# LEDMulti.net
KiCad netlist of a schematic drawn in Altium Designer
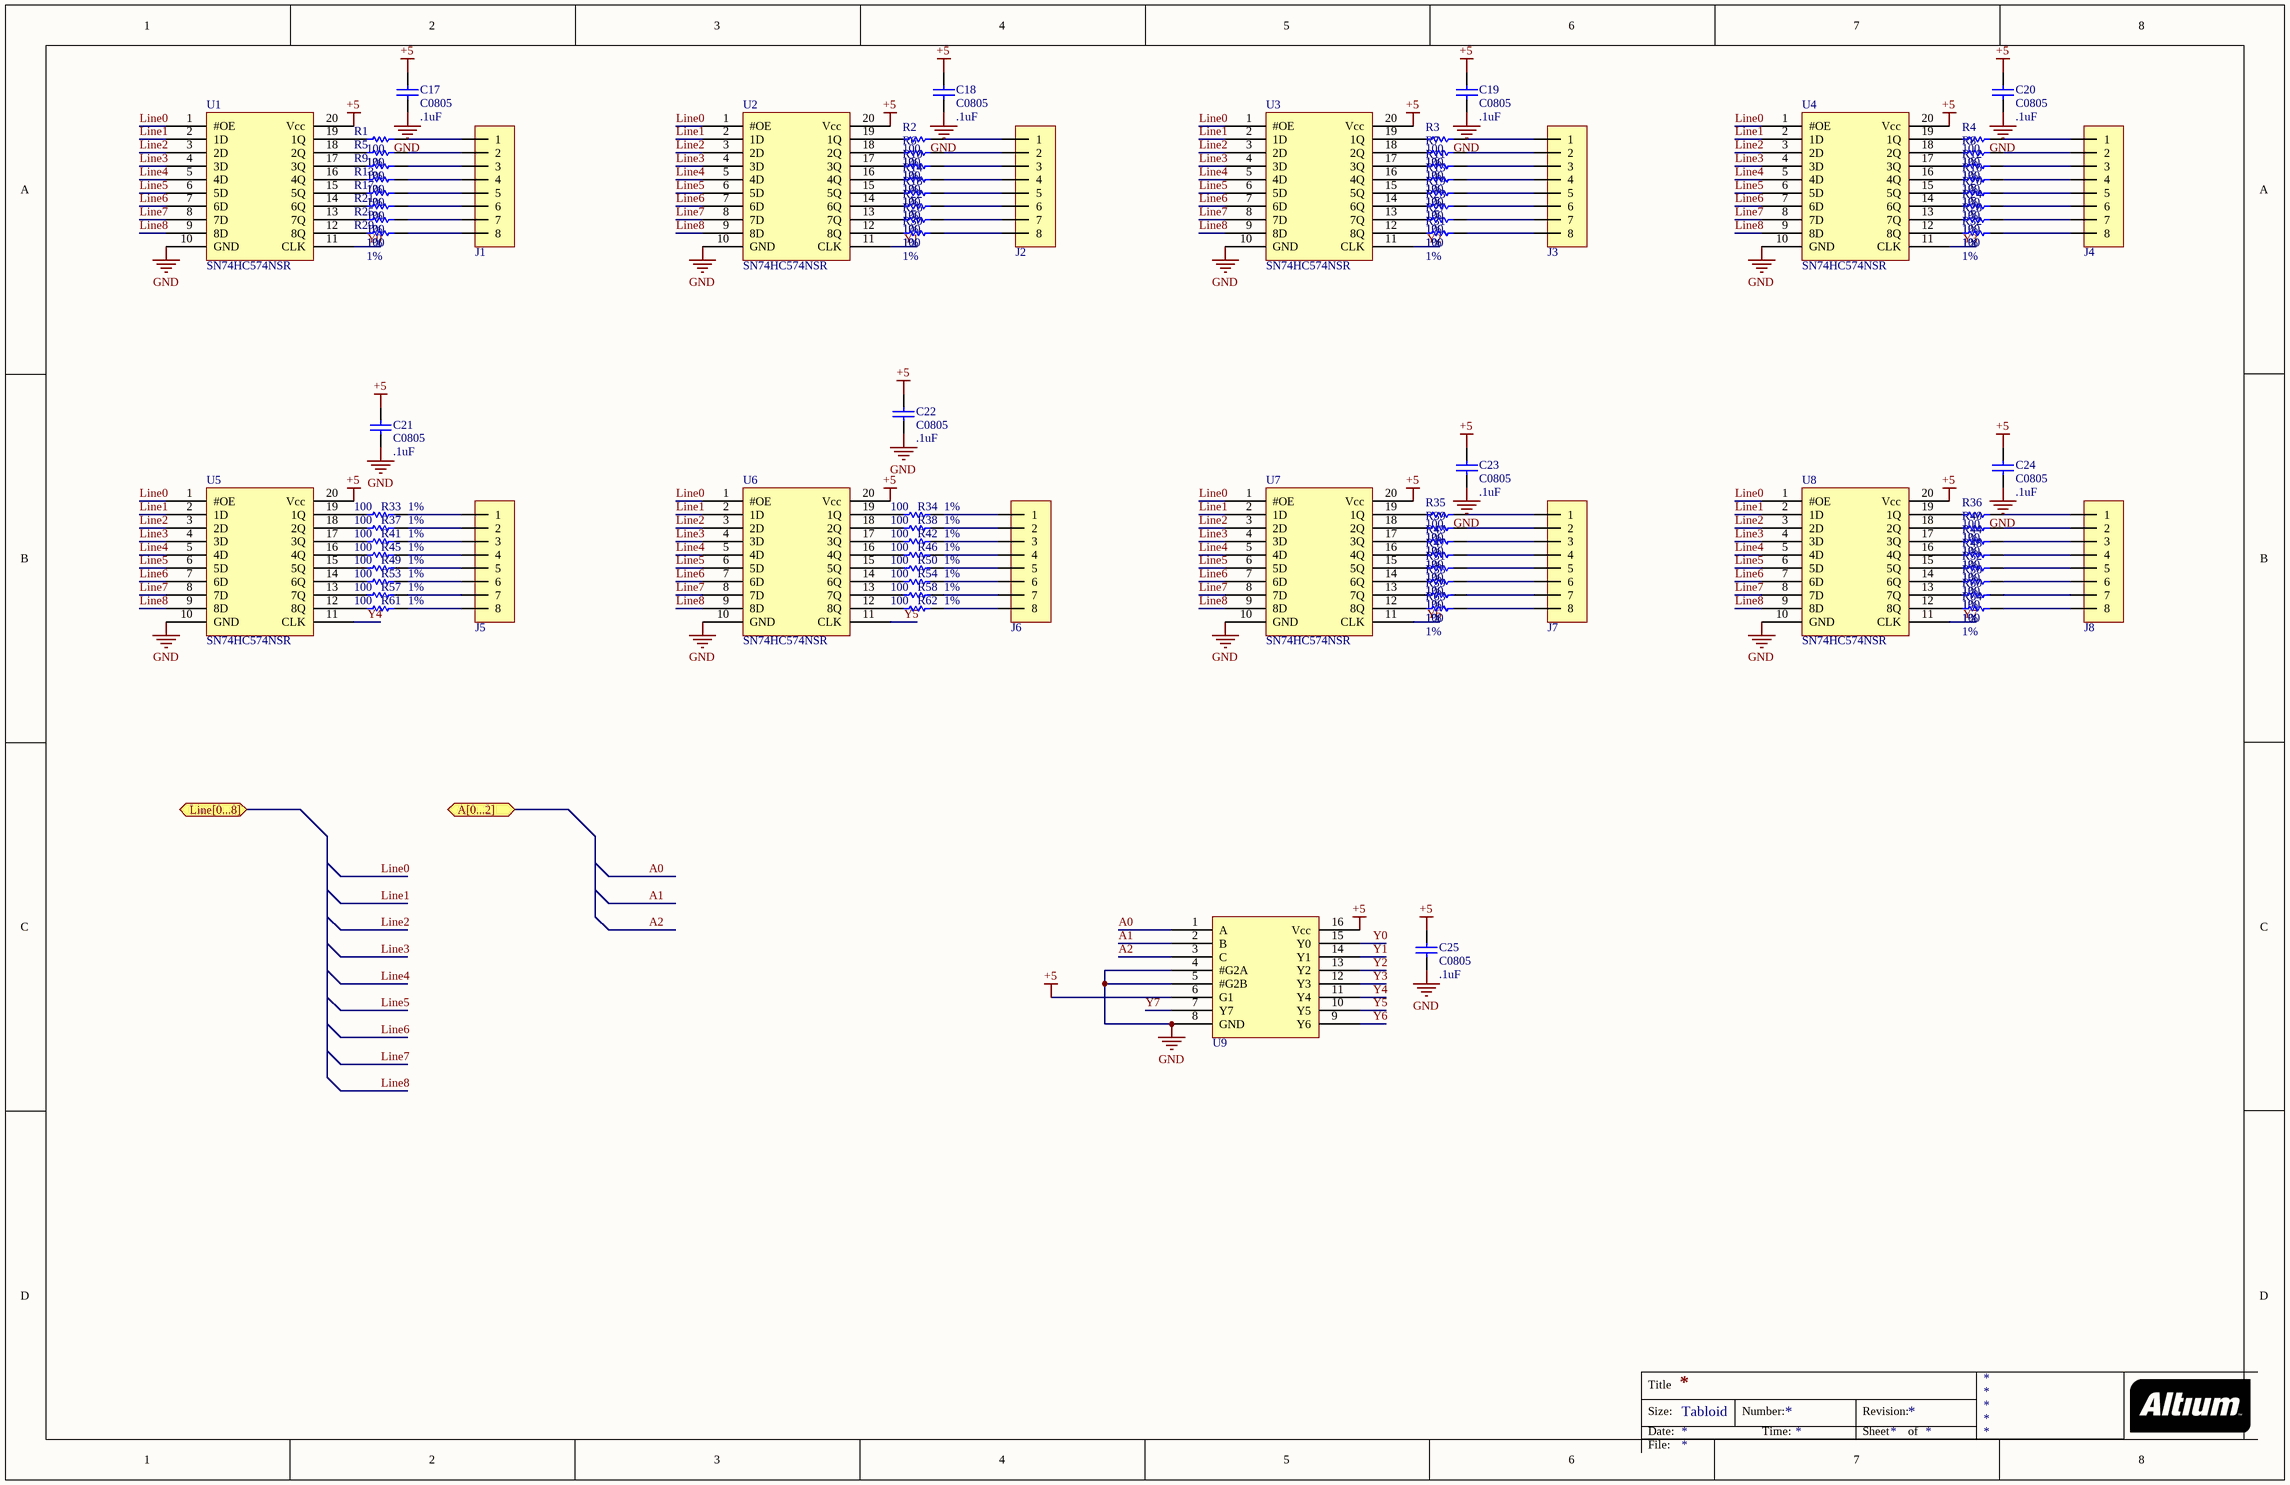
[diagram p0: LEDMulti.SchDoc]

(export (version "E")
  (design (tool "Eeschema 10.0.6"))
  (components
    (comp (ref "C17")
      (value "C0805")
      (footprint "0805")
      (description "Ceramic Chip Capacitor - Standard")
      (fields (field (name "ALTIUM_VALUE") ".1uF") (field (name "PUBLISHER") "Altium Limited"))
      (libsource (lib "KEMET Chip Capacitor") (part "C0805"))
    )
    (comp (ref "C18")
      (value "C0805")
      (footprint "0805")
      (description "Ceramic Chip Capacitor - Standard")
      (fields (field (name "ALTIUM_VALUE") ".1uF") (field (name "PUBLISHER") "Altium Limited"))
      (libsource (lib "KEMET Chip Capacitor") (part "C0805"))
    )
    (comp (ref "C19")
      (value "C0805")
      (footprint "0805")
      (description "Ceramic Chip Capacitor - Standard")
      (fields (field (name "ALTIUM_VALUE") ".1uF") (field (name "PUBLISHER") "Altium Limited"))
      (libsource (lib "KEMET Chip Capacitor") (part "C0805"))
    )
    (comp (ref "C20")
      (value "C0805")
      (footprint "0805")
      (description "Ceramic Chip Capacitor - Standard")
      (fields (field (name "ALTIUM_VALUE") ".1uF") (field (name "PUBLISHER") "Altium Limited"))
      (libsource (lib "KEMET Chip Capacitor") (part "C0805"))
    )
    (comp (ref "C21")
      (value "C0805")
      (footprint "0805")
      (description "Ceramic Chip Capacitor - Standard")
      (fields (field (name "ALTIUM_VALUE") ".1uF") (field (name "PUBLISHER") "Altium Limited"))
      (libsource (lib "KEMET Chip Capacitor") (part "C0805"))
    )
    (comp (ref "C22")
      (value "C0805")
      (footprint "0805")
      (description "Ceramic Chip Capacitor - Standard")
      (fields (field (name "ALTIUM_VALUE") ".1uF") (field (name "PUBLISHER") "Altium Limited"))
      (libsource (lib "KEMET Chip Capacitor") (part "C0805"))
    )
    (comp (ref "C23")
      (value "C0805")
      (footprint "0805")
      (description "Ceramic Chip Capacitor - Standard")
      (fields (field (name "ALTIUM_VALUE") ".1uF") (field (name "PUBLISHER") "Altium Limited"))
      (libsource (lib "KEMET Chip Capacitor") (part "C0805"))
    )
    (comp (ref "C24")
      (value "C0805")
      (footprint "0805")
      (description "Ceramic Chip Capacitor - Standard")
      (fields (field (name "ALTIUM_VALUE") ".1uF") (field (name "PUBLISHER") "Altium Limited"))
      (libsource (lib "KEMET Chip Capacitor") (part "C0805"))
    )
    (comp (ref "C25")
      (value "C0805")
      (footprint "0805")
      (description "Ceramic Chip Capacitor - Standard")
      (fields (field (name "ALTIUM_VALUE") ".1uF") (field (name "PUBLISHER") "Altium Limited"))
      (libsource (lib "KEMET Chip Capacitor") (part "C0805"))
    )
    (comp (ref "J1")
      (value "8x1 Male Header Pin")
      (footprint "Male 8x1")
      (description "8x1 100mil Header")
      (libsource (lib "LEDCube") (part "8x1 Male Header Pin"))
    )
    (comp (ref "J2")
      (value "8x1 Male Header Pin")
      (footprint "Male 8x1")
      (description "8x1 100mil Header")
      (libsource (lib "LEDCube") (part "8x1 Male Header Pin"))
    )
    (comp (ref "J3")
      (value "8x1 Male Header Pin")
      (footprint "Male 8x1")
      (description "8x1 100mil Header")
      (libsource (lib "LEDCube") (part "8x1 Male Header Pin"))
    )
    (comp (ref "J4")
      (value "8x1 Male Header Pin")
      (footprint "Male 8x1")
      (description "8x1 100mil Header")
      (libsource (lib "LEDCube") (part "8x1 Male Header Pin"))
    )
    (comp (ref "J5")
      (value "8x1 Male Header Pin")
      (footprint "Male 8x1")
      (description "8x1 100mil Header")
      (libsource (lib "LEDCube") (part "8x1 Male Header Pin"))
    )
    (comp (ref "J6")
      (value "8x1 Male Header Pin")
      (footprint "Male 8x1")
      (description "8x1 100mil Header")
      (libsource (lib "LEDCube") (part "8x1 Male Header Pin"))
    )
    (comp (ref "J7")
      (value "8x1 Male Header Pin")
      (footprint "Male 8x1")
      (description "8x1 100mil Header")
      (libsource (lib "LEDCube") (part "8x1 Male Header Pin"))
    )
    (comp (ref "J8")
      (value "8x1 Male Header Pin")
      (footprint "Male 8x1")
      (description "8x1 100mil Header")
      (libsource (lib "LEDCube") (part "8x1 Male Header Pin"))
    )
    (comp (ref "R1")
      (value "100")
      (footprint "R 0805 (2012) RESISTOR")
      (fields (field (name "TOLERANCE") "1%"))
      (libsource (lib "LEDCube") (part "RES 0805 1K 1%"))
    )
    (comp (ref "R2")
      (value "100")
      (footprint "R 0805 (2012) RESISTOR")
      (fields (field (name "TOLERANCE") "1%"))
      (libsource (lib "LEDCube") (part "RES 0805 1K 1%"))
    )
    (comp (ref "R3")
      (value "100")
      (footprint "R 0805 (2012) RESISTOR")
      (fields (field (name "TOLERANCE") "1%"))
      (libsource (lib "LEDCube") (part "RES 0805 1K 1%"))
    )
    (comp (ref "R4")
      (value "100")
      (footprint "R 0805 (2012) RESISTOR")
      (fields (field (name "TOLERANCE") "1%"))
      (libsource (lib "LEDCube") (part "RES 0805 1K 1%"))
    )
    (comp (ref "R5")
      (value "100")
      (footprint "R 0805 (2012) RESISTOR")
      (fields (field (name "TOLERANCE") "1%"))
      (libsource (lib "LEDCube") (part "RES 0805 1K 1%"))
    )
    (comp (ref "R6")
      (value "100")
      (footprint "R 0805 (2012) RESISTOR")
      (fields (field (name "TOLERANCE") "1%"))
      (libsource (lib "LEDCube") (part "RES 0805 1K 1%"))
    )
    (comp (ref "R7")
      (value "100")
      (footprint "R 0805 (2012) RESISTOR")
      (fields (field (name "TOLERANCE") "1%"))
      (libsource (lib "LEDCube") (part "RES 0805 1K 1%"))
    )
    (comp (ref "R8")
      (value "100")
      (footprint "R 0805 (2012) RESISTOR")
      (fields (field (name "TOLERANCE") "1%"))
      (libsource (lib "LEDCube") (part "RES 0805 1K 1%"))
    )
    (comp (ref "R9")
      (value "100")
      (footprint "R 0805 (2012) RESISTOR")
      (fields (field (name "TOLERANCE") "1%"))
      (libsource (lib "LEDCube") (part "RES 0805 1K 1%"))
    )
    (comp (ref "R10")
      (value "100")
      (footprint "R 0805 (2012) RESISTOR")
      (fields (field (name "TOLERANCE") "1%"))
      (libsource (lib "LEDCube") (part "RES 0805 1K 1%"))
    )
    (comp (ref "R11")
      (value "100")
      (footprint "R 0805 (2012) RESISTOR")
      (fields (field (name "TOLERANCE") "1%"))
      (libsource (lib "LEDCube") (part "RES 0805 1K 1%"))
    )
    (comp (ref "R12")
      (value "100")
      (footprint "R 0805 (2012) RESISTOR")
      (fields (field (name "TOLERANCE") "1%"))
      (libsource (lib "LEDCube") (part "RES 0805 1K 1%"))
    )
    (comp (ref "R13")
      (value "100")
      (footprint "R 0805 (2012) RESISTOR")
      (fields (field (name "TOLERANCE") "1%"))
      (libsource (lib "LEDCube") (part "RES 0805 1K 1%"))
    )
    (comp (ref "R14")
      (value "100")
      (footprint "R 0805 (2012) RESISTOR")
      (fields (field (name "TOLERANCE") "1%"))
      (libsource (lib "LEDCube") (part "RES 0805 1K 1%"))
    )
    (comp (ref "R15")
      (value "100")
      (footprint "R 0805 (2012) RESISTOR")
      (fields (field (name "TOLERANCE") "1%"))
      (libsource (lib "LEDCube") (part "RES 0805 1K 1%"))
    )
    (comp (ref "R16")
      (value "100")
      (footprint "R 0805 (2012) RESISTOR")
      (fields (field (name "TOLERANCE") "1%"))
      (libsource (lib "LEDCube") (part "RES 0805 1K 1%"))
    )
    (comp (ref "R17")
      (value "100")
      (footprint "R 0805 (2012) RESISTOR")
      (fields (field (name "TOLERANCE") "1%"))
      (libsource (lib "LEDCube") (part "RES 0805 1K 1%"))
    )
    (comp (ref "R18")
      (value "100")
      (footprint "R 0805 (2012) RESISTOR")
      (fields (field (name "TOLERANCE") "1%"))
      (libsource (lib "LEDCube") (part "RES 0805 1K 1%"))
    )
    (comp (ref "R19")
      (value "100")
      (footprint "R 0805 (2012) RESISTOR")
      (fields (field (name "TOLERANCE") "1%"))
      (libsource (lib "LEDCube") (part "RES 0805 1K 1%"))
    )
    (comp (ref "R20")
      (value "100")
      (footprint "R 0805 (2012) RESISTOR")
      (fields (field (name "TOLERANCE") "1%"))
      (libsource (lib "LEDCube") (part "RES 0805 1K 1%"))
    )
    (comp (ref "R21")
      (value "100")
      (footprint "R 0805 (2012) RESISTOR")
      (fields (field (name "TOLERANCE") "1%"))
      (libsource (lib "LEDCube") (part "RES 0805 1K 1%"))
    )
    (comp (ref "R22")
      (value "100")
      (footprint "R 0805 (2012) RESISTOR")
      (fields (field (name "TOLERANCE") "1%"))
      (libsource (lib "LEDCube") (part "RES 0805 1K 1%"))
    )
    (comp (ref "R23")
      (value "100")
      (footprint "R 0805 (2012) RESISTOR")
      (fields (field (name "TOLERANCE") "1%"))
      (libsource (lib "LEDCube") (part "RES 0805 1K 1%"))
    )
    (comp (ref "R24")
      (value "100")
      (footprint "R 0805 (2012) RESISTOR")
      (fields (field (name "TOLERANCE") "1%"))
      (libsource (lib "LEDCube") (part "RES 0805 1K 1%"))
    )
    (comp (ref "R25")
      (value "100")
      (footprint "R 0805 (2012) RESISTOR")
      (fields (field (name "TOLERANCE") "1%"))
      (libsource (lib "LEDCube") (part "RES 0805 1K 1%"))
    )
    (comp (ref "R26")
      (value "100")
      (footprint "R 0805 (2012) RESISTOR")
      (fields (field (name "TOLERANCE") "1%"))
      (libsource (lib "LEDCube") (part "RES 0805 1K 1%"))
    )
    (comp (ref "R27")
      (value "100")
      (footprint "R 0805 (2012) RESISTOR")
      (fields (field (name "TOLERANCE") "1%"))
      (libsource (lib "LEDCube") (part "RES 0805 1K 1%"))
    )
    (comp (ref "R28")
      (value "100")
      (footprint "R 0805 (2012) RESISTOR")
      (fields (field (name "TOLERANCE") "1%"))
      (libsource (lib "LEDCube") (part "RES 0805 1K 1%"))
    )
    (comp (ref "R29")
      (value "100")
      (footprint "R 0805 (2012) RESISTOR")
      (fields (field (name "TOLERANCE") "1%"))
      (libsource (lib "LEDCube") (part "RES 0805 1K 1%"))
    )
    (comp (ref "R30")
      (value "100")
      (footprint "R 0805 (2012) RESISTOR")
      (fields (field (name "TOLERANCE") "1%"))
      (libsource (lib "LEDCube") (part "RES 0805 1K 1%"))
    )
    (comp (ref "R31")
      (value "100")
      (footprint "R 0805 (2012) RESISTOR")
      (fields (field (name "TOLERANCE") "1%"))
      (libsource (lib "LEDCube") (part "RES 0805 1K 1%"))
    )
    (comp (ref "R32")
      (value "100")
      (footprint "R 0805 (2012) RESISTOR")
      (fields (field (name "TOLERANCE") "1%"))
      (libsource (lib "LEDCube") (part "RES 0805 1K 1%"))
    )
    (comp (ref "R33")
      (value "100")
      (footprint "R 0805 (2012) RESISTOR")
      (fields (field (name "TOLERANCE") "1%"))
      (libsource (lib "LEDCube") (part "RES 0805 1K 1%"))
    )
    (comp (ref "R34")
      (value "100")
      (footprint "R 0805 (2012) RESISTOR")
      (fields (field (name "TOLERANCE") "1%"))
      (libsource (lib "LEDCube") (part "RES 0805 1K 1%"))
    )
    (comp (ref "R35")
      (value "100")
      (footprint "R 0805 (2012) RESISTOR")
      (fields (field (name "TOLERANCE") "1%"))
      (libsource (lib "LEDCube") (part "RES 0805 1K 1%"))
    )
    (comp (ref "R36")
      (value "100")
      (footprint "R 0805 (2012) RESISTOR")
      (fields (field (name "TOLERANCE") "1%"))
      (libsource (lib "LEDCube") (part "RES 0805 1K 1%"))
    )
    (comp (ref "R37")
      (value "100")
      (footprint "R 0805 (2012) RESISTOR")
      (fields (field (name "TOLERANCE") "1%"))
      (libsource (lib "LEDCube") (part "RES 0805 1K 1%"))
    )
    (comp (ref "R38")
      (value "100")
      (footprint "R 0805 (2012) RESISTOR")
      (fields (field (name "TOLERANCE") "1%"))
      (libsource (lib "LEDCube") (part "RES 0805 1K 1%"))
    )
    (comp (ref "R39")
      (value "100")
      (footprint "R 0805 (2012) RESISTOR")
      (fields (field (name "TOLERANCE") "1%"))
      (libsource (lib "LEDCube") (part "RES 0805 1K 1%"))
    )
    (comp (ref "R40")
      (value "100")
      (footprint "R 0805 (2012) RESISTOR")
      (fields (field (name "TOLERANCE") "1%"))
      (libsource (lib "LEDCube") (part "RES 0805 1K 1%"))
    )
    (comp (ref "R41")
      (value "100")
      (footprint "R 0805 (2012) RESISTOR")
      (fields (field (name "TOLERANCE") "1%"))
      (libsource (lib "LEDCube") (part "RES 0805 1K 1%"))
    )
    (comp (ref "R42")
      (value "100")
      (footprint "R 0805 (2012) RESISTOR")
      (fields (field (name "TOLERANCE") "1%"))
      (libsource (lib "LEDCube") (part "RES 0805 1K 1%"))
    )
    (comp (ref "R43")
      (value "100")
      (footprint "R 0805 (2012) RESISTOR")
      (fields (field (name "TOLERANCE") "1%"))
      (libsource (lib "LEDCube") (part "RES 0805 1K 1%"))
    )
    (comp (ref "R44")
      (value "100")
      (footprint "R 0805 (2012) RESISTOR")
      (fields (field (name "TOLERANCE") "1%"))
      (libsource (lib "LEDCube") (part "RES 0805 1K 1%"))
    )
    (comp (ref "R45")
      (value "100")
      (footprint "R 0805 (2012) RESISTOR")
      (fields (field (name "TOLERANCE") "1%"))
      (libsource (lib "LEDCube") (part "RES 0805 1K 1%"))
    )
    (comp (ref "R46")
      (value "100")
      (footprint "R 0805 (2012) RESISTOR")
      (fields (field (name "TOLERANCE") "1%"))
      (libsource (lib "LEDCube") (part "RES 0805 1K 1%"))
    )
    (comp (ref "R47")
      (value "100")
      (footprint "R 0805 (2012) RESISTOR")
      (fields (field (name "TOLERANCE") "1%"))
      (libsource (lib "LEDCube") (part "RES 0805 1K 1%"))
    )
    (comp (ref "R48")
      (value "100")
      (footprint "R 0805 (2012) RESISTOR")
      (fields (field (name "TOLERANCE") "1%"))
      (libsource (lib "LEDCube") (part "RES 0805 1K 1%"))
    )
    (comp (ref "R49")
      (value "100")
      (footprint "R 0805 (2012) RESISTOR")
      (fields (field (name "TOLERANCE") "1%"))
      (libsource (lib "LEDCube") (part "RES 0805 1K 1%"))
    )
    (comp (ref "R50")
      (value "100")
      (footprint "R 0805 (2012) RESISTOR")
      (fields (field (name "TOLERANCE") "1%"))
      (libsource (lib "LEDCube") (part "RES 0805 1K 1%"))
    )
    (comp (ref "R51")
      (value "100")
      (footprint "R 0805 (2012) RESISTOR")
      (fields (field (name "TOLERANCE") "1%"))
      (libsource (lib "LEDCube") (part "RES 0805 1K 1%"))
    )
    (comp (ref "R52")
      (value "100")
      (footprint "R 0805 (2012) RESISTOR")
      (fields (field (name "TOLERANCE") "1%"))
      (libsource (lib "LEDCube") (part "RES 0805 1K 1%"))
    )
    (comp (ref "R53")
      (value "100")
      (footprint "R 0805 (2012) RESISTOR")
      (fields (field (name "TOLERANCE") "1%"))
      (libsource (lib "LEDCube") (part "RES 0805 1K 1%"))
    )
    (comp (ref "R54")
      (value "100")
      (footprint "R 0805 (2012) RESISTOR")
      (fields (field (name "TOLERANCE") "1%"))
      (libsource (lib "LEDCube") (part "RES 0805 1K 1%"))
    )
    (comp (ref "R55")
      (value "100")
      (footprint "R 0805 (2012) RESISTOR")
      (fields (field (name "TOLERANCE") "1%"))
      (libsource (lib "LEDCube") (part "RES 0805 1K 1%"))
    )
    (comp (ref "R56")
      (value "100")
      (footprint "R 0805 (2012) RESISTOR")
      (fields (field (name "TOLERANCE") "1%"))
      (libsource (lib "LEDCube") (part "RES 0805 1K 1%"))
    )
    (comp (ref "R57")
      (value "100")
      (footprint "R 0805 (2012) RESISTOR")
      (fields (field (name "TOLERANCE") "1%"))
      (libsource (lib "LEDCube") (part "RES 0805 1K 1%"))
    )
    (comp (ref "R58")
      (value "100")
      (footprint "R 0805 (2012) RESISTOR")
      (fields (field (name "TOLERANCE") "1%"))
      (libsource (lib "LEDCube") (part "RES 0805 1K 1%"))
    )
    (comp (ref "R59")
      (value "100")
      (footprint "R 0805 (2012) RESISTOR")
      (fields (field (name "TOLERANCE") "1%"))
      (libsource (lib "LEDCube") (part "RES 0805 1K 1%"))
    )
    (comp (ref "R60")
      (value "100")
      (footprint "R 0805 (2012) RESISTOR")
      (fields (field (name "TOLERANCE") "1%"))
      (libsource (lib "LEDCube") (part "RES 0805 1K 1%"))
    )
    (comp (ref "R61")
      (value "100")
      (footprint "R 0805 (2012) RESISTOR")
      (fields (field (name "TOLERANCE") "1%"))
      (libsource (lib "LEDCube") (part "RES 0805 1K 1%"))
    )
    (comp (ref "R62")
      (value "100")
      (footprint "R 0805 (2012) RESISTOR")
      (fields (field (name "TOLERANCE") "1%"))
      (libsource (lib "LEDCube") (part "RES 0805 1K 1%"))
    )
    (comp (ref "R63")
      (value "100")
      (footprint "R 0805 (2012) RESISTOR")
      (fields (field (name "TOLERANCE") "1%"))
      (libsource (lib "LEDCube") (part "RES 0805 1K 1%"))
    )
    (comp (ref "R64")
      (value "100")
      (footprint "R 0805 (2012) RESISTOR")
      (fields (field (name "TOLERANCE") "1%"))
      (libsource (lib "LEDCube") (part "RES 0805 1K 1%"))
    )
    (comp (ref "U1")
      (value "SN74HC574NSR")
      (footprint "TSSOP 20")
      (description "IC D-TYPE POS TRG SNGL 20SO")
      (libsource (lib "LEDCube") (part "SN74HC574NSR"))
    )
    (comp (ref "U2")
      (value "SN74HC574NSR")
      (footprint "TSSOP 20")
      (description "IC D-TYPE POS TRG SNGL 20SO")
      (libsource (lib "LEDCube") (part "SN74HC574NSR"))
    )
    (comp (ref "U3")
      (value "SN74HC574NSR")
      (footprint "TSSOP 20")
      (description "IC D-TYPE POS TRG SNGL 20SO")
      (libsource (lib "LEDCube") (part "SN74HC574NSR"))
    )
    (comp (ref "U4")
      (value "SN74HC574NSR")
      (footprint "TSSOP 20")
      (description "IC D-TYPE POS TRG SNGL 20SO")
      (libsource (lib "LEDCube") (part "SN74HC574NSR"))
    )
    (comp (ref "U5")
      (value "SN74HC574NSR")
      (footprint "TSSOP 20")
      (description "IC D-TYPE POS TRG SNGL 20SO")
      (libsource (lib "LEDCube") (part "SN74HC574NSR"))
    )
    (comp (ref "U6")
      (value "SN74HC574NSR")
      (footprint "TSSOP 20")
      (description "IC D-TYPE POS TRG SNGL 20SO")
      (libsource (lib "LEDCube") (part "SN74HC574NSR"))
    )
    (comp (ref "U7")
      (value "SN74HC574NSR")
      (footprint "TSSOP 20")
      (description "IC D-TYPE POS TRG SNGL 20SO")
      (libsource (lib "LEDCube") (part "SN74HC574NSR"))
    )
    (comp (ref "U8")
      (value "SN74HC574NSR")
      (footprint "TSSOP 20")
      (description "IC D-TYPE POS TRG SNGL 20SO")
      (libsource (lib "LEDCube") (part "SN74HC574NSR"))
    )
    (comp (ref "U9")
      (value "SN74HC138N")
      (footprint "SOP16")
      (description "IC DECODER/DEMUX 3-8 LINE 16SO")
      (libsource (lib "LEDCube") (part "SN4HC138N"))
    )
  )
  (nets
    (net (code "1") (name "+5") (class "Default")
      (node (ref "C17") (pin "2") (pinfunction "2_2") (pintype "passive"))
      (node (ref "C18") (pin "2") (pinfunction "2_2") (pintype "passive"))
      (node (ref "C19") (pin "2") (pinfunction "2_2") (pintype "passive"))
      (node (ref "C20") (pin "2") (pinfunction "2_2") (pintype "passive"))
      (node (ref "C21") (pin "2") (pinfunction "2_2") (pintype "passive"))
      (node (ref "C22") (pin "2") (pinfunction "2_2") (pintype "passive"))
      (node (ref "C23") (pin "2") (pinfunction "2_2") (pintype "passive"))
      (node (ref "C24") (pin "2") (pinfunction "2_2") (pintype "passive"))
      (node (ref "C25") (pin "2") (pinfunction "2_2") (pintype "passive"))
      (node (ref "U1") (pin "20") (pinfunction "Vcc_20") (pintype "power_in"))
      (node (ref "U2") (pin "20") (pinfunction "Vcc_20") (pintype "power_in"))
      (node (ref "U3") (pin "20") (pinfunction "Vcc_20") (pintype "power_in"))
      (node (ref "U4") (pin "20") (pinfunction "Vcc_20") (pintype "power_in"))
      (node (ref "U5") (pin "20") (pinfunction "Vcc_20") (pintype "power_in"))
      (node (ref "U6") (pin "20") (pinfunction "Vcc_20") (pintype "power_in"))
      (node (ref "U7") (pin "20") (pinfunction "Vcc_20") (pintype "power_in"))
      (node (ref "U8") (pin "20") (pinfunction "Vcc_20") (pintype "power_in"))
      (node (ref "U9") (pin "16") (pinfunction "Vcc_16") (pintype "power_in"))
      (node (ref "U9") (pin "6") (pinfunction "G1_6") (pintype "passive"))
    )
    (net (code "2") (name "/A0") (class "Default")
      (node (ref "U9") (pin "1") (pinfunction "A_1") (pintype "passive"))
    )
    (net (code "3") (name "/A1") (class "Default")
      (node (ref "U9") (pin "2") (pinfunction "B_2") (pintype "passive"))
    )
    (net (code "4") (name "/A2") (class "Default")
      (node (ref "U9") (pin "3") (pinfunction "C_3") (pintype "passive"))
    )
    (net (code "6") (name "/Line0") (class "Default")
      (node (ref "U1") (pin "1") (pinfunction "#OE_1") (pintype "passive"))
      (node (ref "U2") (pin "1") (pinfunction "#OE_1") (pintype "passive"))
      (node (ref "U3") (pin "1") (pinfunction "#OE_1") (pintype "passive"))
      (node (ref "U4") (pin "1") (pinfunction "#OE_1") (pintype "passive"))
      (node (ref "U5") (pin "1") (pinfunction "#OE_1") (pintype "passive"))
      (node (ref "U6") (pin "1") (pinfunction "#OE_1") (pintype "passive"))
      (node (ref "U7") (pin "1") (pinfunction "#OE_1") (pintype "passive"))
      (node (ref "U8") (pin "1") (pinfunction "#OE_1") (pintype "passive"))
    )
    (net (code "7") (name "/Line1") (class "Default")
      (node (ref "U1") (pin "2") (pinfunction "1D_2") (pintype "passive"))
      (node (ref "U2") (pin "2") (pinfunction "1D_2") (pintype "passive"))
      (node (ref "U3") (pin "2") (pinfunction "1D_2") (pintype "passive"))
      (node (ref "U4") (pin "2") (pinfunction "1D_2") (pintype "passive"))
      (node (ref "U5") (pin "2") (pinfunction "1D_2") (pintype "passive"))
      (node (ref "U6") (pin "2") (pinfunction "1D_2") (pintype "passive"))
      (node (ref "U7") (pin "2") (pinfunction "1D_2") (pintype "passive"))
      (node (ref "U8") (pin "2") (pinfunction "1D_2") (pintype "passive"))
    )
    (net (code "8") (name "/Line2") (class "Default")
      (node (ref "U1") (pin "3") (pinfunction "2D_3") (pintype "passive"))
      (node (ref "U2") (pin "3") (pinfunction "2D_3") (pintype "passive"))
      (node (ref "U3") (pin "3") (pinfunction "2D_3") (pintype "passive"))
      (node (ref "U4") (pin "3") (pinfunction "2D_3") (pintype "passive"))
      (node (ref "U5") (pin "3") (pinfunction "2D_3") (pintype "passive"))
      (node (ref "U6") (pin "3") (pinfunction "2D_3") (pintype "passive"))
      (node (ref "U7") (pin "3") (pinfunction "2D_3") (pintype "passive"))
      (node (ref "U8") (pin "3") (pinfunction "2D_3") (pintype "passive"))
    )
    (net (code "9") (name "/Line3") (class "Default")
      (node (ref "U1") (pin "4") (pinfunction "3D_4") (pintype "passive"))
      (node (ref "U2") (pin "4") (pinfunction "3D_4") (pintype "passive"))
      (node (ref "U3") (pin "4") (pinfunction "3D_4") (pintype "passive"))
      (node (ref "U4") (pin "4") (pinfunction "3D_4") (pintype "passive"))
      (node (ref "U5") (pin "4") (pinfunction "3D_4") (pintype "passive"))
      (node (ref "U6") (pin "4") (pinfunction "3D_4") (pintype "passive"))
      (node (ref "U7") (pin "4") (pinfunction "3D_4") (pintype "passive"))
      (node (ref "U8") (pin "4") (pinfunction "3D_4") (pintype "passive"))
    )
    (net (code "10") (name "/Line4") (class "Default")
      (node (ref "U1") (pin "5") (pinfunction "4D_5") (pintype "passive"))
      (node (ref "U2") (pin "5") (pinfunction "4D_5") (pintype "passive"))
      (node (ref "U3") (pin "5") (pinfunction "4D_5") (pintype "passive"))
      (node (ref "U4") (pin "5") (pinfunction "4D_5") (pintype "passive"))
      (node (ref "U5") (pin "5") (pinfunction "4D_5") (pintype "passive"))
      (node (ref "U6") (pin "5") (pinfunction "4D_5") (pintype "passive"))
      (node (ref "U7") (pin "5") (pinfunction "4D_5") (pintype "passive"))
      (node (ref "U8") (pin "5") (pinfunction "4D_5") (pintype "passive"))
    )
    (net (code "11") (name "/Line5") (class "Default")
      (node (ref "U1") (pin "6") (pinfunction "5D_6") (pintype "passive"))
      (node (ref "U2") (pin "6") (pinfunction "5D_6") (pintype "passive"))
      (node (ref "U3") (pin "6") (pinfunction "5D_6") (pintype "passive"))
      (node (ref "U4") (pin "6") (pinfunction "5D_6") (pintype "passive"))
      (node (ref "U5") (pin "6") (pinfunction "5D_6") (pintype "passive"))
      (node (ref "U6") (pin "6") (pinfunction "5D_6") (pintype "passive"))
      (node (ref "U7") (pin "6") (pinfunction "5D_6") (pintype "passive"))
      (node (ref "U8") (pin "6") (pinfunction "5D_6") (pintype "passive"))
    )
    (net (code "12") (name "/Line6") (class "Default")
      (node (ref "U1") (pin "7") (pinfunction "6D_7") (pintype "passive"))
      (node (ref "U2") (pin "7") (pinfunction "6D_7") (pintype "passive"))
      (node (ref "U3") (pin "7") (pinfunction "6D_7") (pintype "passive"))
      (node (ref "U4") (pin "7") (pinfunction "6D_7") (pintype "passive"))
      (node (ref "U5") (pin "7") (pinfunction "6D_7") (pintype "passive"))
      (node (ref "U6") (pin "7") (pinfunction "6D_7") (pintype "passive"))
      (node (ref "U7") (pin "7") (pinfunction "6D_7") (pintype "passive"))
      (node (ref "U8") (pin "7") (pinfunction "6D_7") (pintype "passive"))
    )
    (net (code "13") (name "/Line7") (class "Default")
      (node (ref "U1") (pin "8") (pinfunction "7D_8") (pintype "passive"))
      (node (ref "U2") (pin "8") (pinfunction "7D_8") (pintype "passive"))
      (node (ref "U3") (pin "8") (pinfunction "7D_8") (pintype "passive"))
      (node (ref "U4") (pin "8") (pinfunction "7D_8") (pintype "passive"))
      (node (ref "U5") (pin "8") (pinfunction "7D_8") (pintype "passive"))
      (node (ref "U6") (pin "8") (pinfunction "7D_8") (pintype "passive"))
      (node (ref "U7") (pin "8") (pinfunction "7D_8") (pintype "passive"))
      (node (ref "U8") (pin "8") (pinfunction "7D_8") (pintype "passive"))
    )
    (net (code "14") (name "/Line8") (class "Default")
      (node (ref "U1") (pin "9") (pinfunction "8D_9") (pintype "passive"))
      (node (ref "U2") (pin "9") (pinfunction "8D_9") (pintype "passive"))
      (node (ref "U3") (pin "9") (pinfunction "8D_9") (pintype "passive"))
      (node (ref "U4") (pin "9") (pinfunction "8D_9") (pintype "passive"))
      (node (ref "U5") (pin "9") (pinfunction "8D_9") (pintype "passive"))
      (node (ref "U6") (pin "9") (pinfunction "8D_9") (pintype "passive"))
      (node (ref "U7") (pin "9") (pinfunction "8D_9") (pintype "passive"))
      (node (ref "U8") (pin "9") (pinfunction "8D_9") (pintype "passive"))
    )
    (net (code "16") (name "/Y0") (class "Default")
      (node (ref "U1") (pin "11") (pinfunction "CLK_11") (pintype "passive"))
      (node (ref "U9") (pin "15") (pinfunction "Y0_15") (pintype "passive"))
    )
    (net (code "17") (name "/Y1") (class "Default")
      (node (ref "U2") (pin "11") (pinfunction "CLK_11") (pintype "passive"))
      (node (ref "U9") (pin "14") (pinfunction "Y1_14") (pintype "passive"))
    )
    (net (code "18") (name "/Y2") (class "Default")
      (node (ref "U3") (pin "11") (pinfunction "CLK_11") (pintype "passive"))
      (node (ref "U9") (pin "13") (pinfunction "Y2_13") (pintype "passive"))
    )
    (net (code "19") (name "/Y3") (class "Default")
      (node (ref "U4") (pin "11") (pinfunction "CLK_11") (pintype "passive"))
      (node (ref "U9") (pin "12") (pinfunction "Y3_12") (pintype "passive"))
    )
    (net (code "20") (name "/Y4") (class "Default")
      (node (ref "U5") (pin "11") (pinfunction "CLK_11") (pintype "passive"))
      (node (ref "U9") (pin "11") (pinfunction "Y4_11") (pintype "passive"))
    )
    (net (code "21") (name "/Y5") (class "Default")
      (node (ref "U6") (pin "11") (pinfunction "CLK_11") (pintype "passive"))
      (node (ref "U9") (pin "10") (pinfunction "Y5_10") (pintype "passive"))
    )
    (net (code "22") (name "/Y6") (class "Default")
      (node (ref "U7") (pin "11") (pinfunction "CLK_11") (pintype "passive"))
      (node (ref "U9") (pin "9") (pinfunction "Y6_9") (pintype "passive"))
    )
    (net (code "23") (name "/Y7") (class "Default")
      (node (ref "U8") (pin "11") (pinfunction "CLK_11") (pintype "passive"))
      (node (ref "U9") (pin "7") (pinfunction "Y7_7") (pintype "passive"))
    )
    (net (code "24") (name "GND") (class "Default")
      (node (ref "C17") (pin "1") (pinfunction "1_1") (pintype "passive"))
      (node (ref "C18") (pin "1") (pinfunction "1_1") (pintype "passive"))
      (node (ref "C19") (pin "1") (pinfunction "1_1") (pintype "passive"))
      (node (ref "C20") (pin "1") (pinfunction "1_1") (pintype "passive"))
      (node (ref "C21") (pin "1") (pinfunction "1_1") (pintype "passive"))
      (node (ref "C22") (pin "1") (pinfunction "1_1") (pintype "passive"))
      (node (ref "C23") (pin "1") (pinfunction "1_1") (pintype "passive"))
      (node (ref "C24") (pin "1") (pinfunction "1_1") (pintype "passive"))
      (node (ref "C25") (pin "1") (pinfunction "1_1") (pintype "passive"))
      (node (ref "U1") (pin "10") (pinfunction "GND_10") (pintype "power_in"))
      (node (ref "U2") (pin "10") (pinfunction "GND_10") (pintype "power_in"))
      (node (ref "U3") (pin "10") (pinfunction "GND_10") (pintype "power_in"))
      (node (ref "U4") (pin "10") (pinfunction "GND_10") (pintype "power_in"))
      (node (ref "U5") (pin "10") (pinfunction "GND_10") (pintype "power_in"))
      (node (ref "U6") (pin "10") (pinfunction "GND_10") (pintype "power_in"))
      (node (ref "U7") (pin "10") (pinfunction "GND_10") (pintype "power_in"))
      (node (ref "U8") (pin "10") (pinfunction "GND_10") (pintype "power_in"))
      (node (ref "U9") (pin "4") (pinfunction "#G2A_4") (pintype "passive"))
      (node (ref "U9") (pin "5") (pinfunction "#G2B_5") (pintype "passive"))
      (node (ref "U9") (pin "8") (pinfunction "GND_8") (pintype "power_in"))
    )
    (net (code "25") (name "Net-(J1-Pad1)") (class "Default")
      (node (ref "J1") (pin "1") (pinfunction "1_1") (pintype "passive"))
      (node (ref "R1") (pin "2") (pinfunction "2_2") (pintype "passive"))
    )
    (net (code "26") (name "Net-(J1-Pad2)") (class "Default")
      (node (ref "J1") (pin "2") (pinfunction "2_2") (pintype "passive"))
      (node (ref "R5") (pin "2") (pinfunction "2_2") (pintype "passive"))
    )
    (net (code "27") (name "Net-(J1-Pad3)") (class "Default")
      (node (ref "J1") (pin "3") (pinfunction "3_3") (pintype "passive"))
      (node (ref "R9") (pin "2") (pinfunction "2_2") (pintype "passive"))
    )
    (net (code "28") (name "Net-(J1-Pad4)") (class "Default")
      (node (ref "J1") (pin "4") (pinfunction "4_4") (pintype "passive"))
      (node (ref "R13") (pin "2") (pinfunction "2_2") (pintype "passive"))
    )
    (net (code "29") (name "Net-(J1-Pad5)") (class "Default")
      (node (ref "J1") (pin "5") (pinfunction "5_5") (pintype "passive"))
      (node (ref "R17") (pin "2") (pinfunction "2_2") (pintype "passive"))
    )
    (net (code "30") (name "Net-(J1-Pad6)") (class "Default")
      (node (ref "J1") (pin "6") (pinfunction "6_6") (pintype "passive"))
      (node (ref "R21") (pin "2") (pinfunction "2_2") (pintype "passive"))
    )
    (net (code "31") (name "Net-(J1-Pad7)") (class "Default")
      (node (ref "J1") (pin "7") (pinfunction "7_7") (pintype "passive"))
      (node (ref "R25") (pin "2") (pinfunction "2_2") (pintype "passive"))
    )
    (net (code "32") (name "Net-(J1-Pad8)") (class "Default")
      (node (ref "J1") (pin "8") (pinfunction "8_8") (pintype "passive"))
      (node (ref "R29") (pin "2") (pinfunction "2_2") (pintype "passive"))
    )
    (net (code "33") (name "Net-(J2-Pad1)") (class "Default")
      (node (ref "J2") (pin "1") (pinfunction "1_1") (pintype "passive"))
      (node (ref "R2") (pin "2") (pinfunction "2_2") (pintype "passive"))
    )
    (net (code "34") (name "Net-(J2-Pad2)") (class "Default")
      (node (ref "J2") (pin "2") (pinfunction "2_2") (pintype "passive"))
      (node (ref "R6") (pin "2") (pinfunction "2_2") (pintype "passive"))
    )
    (net (code "35") (name "Net-(J2-Pad3)") (class "Default")
      (node (ref "J2") (pin "3") (pinfunction "3_3") (pintype "passive"))
      (node (ref "R10") (pin "2") (pinfunction "2_2") (pintype "passive"))
    )
    (net (code "36") (name "Net-(J2-Pad4)") (class "Default")
      (node (ref "J2") (pin "4") (pinfunction "4_4") (pintype "passive"))
      (node (ref "R14") (pin "2") (pinfunction "2_2") (pintype "passive"))
    )
    (net (code "37") (name "Net-(J2-Pad5)") (class "Default")
      (node (ref "J2") (pin "5") (pinfunction "5_5") (pintype "passive"))
      (node (ref "R18") (pin "2") (pinfunction "2_2") (pintype "passive"))
    )
    (net (code "38") (name "Net-(J2-Pad6)") (class "Default")
      (node (ref "J2") (pin "6") (pinfunction "6_6") (pintype "passive"))
      (node (ref "R22") (pin "2") (pinfunction "2_2") (pintype "passive"))
    )
    (net (code "39") (name "Net-(J2-Pad7)") (class "Default")
      (node (ref "J2") (pin "7") (pinfunction "7_7") (pintype "passive"))
      (node (ref "R26") (pin "2") (pinfunction "2_2") (pintype "passive"))
    )
    (net (code "40") (name "Net-(J2-Pad8)") (class "Default")
      (node (ref "J2") (pin "8") (pinfunction "8_8") (pintype "passive"))
      (node (ref "R30") (pin "2") (pinfunction "2_2") (pintype "passive"))
    )
    (net (code "41") (name "Net-(J3-Pad1)") (class "Default")
      (node (ref "J3") (pin "1") (pinfunction "1_1") (pintype "passive"))
      (node (ref "R3") (pin "2") (pinfunction "2_2") (pintype "passive"))
    )
    (net (code "42") (name "Net-(J3-Pad2)") (class "Default")
      (node (ref "J3") (pin "2") (pinfunction "2_2") (pintype "passive"))
      (node (ref "R7") (pin "2") (pinfunction "2_2") (pintype "passive"))
    )
    (net (code "43") (name "Net-(J3-Pad3)") (class "Default")
      (node (ref "J3") (pin "3") (pinfunction "3_3") (pintype "passive"))
      (node (ref "R11") (pin "2") (pinfunction "2_2") (pintype "passive"))
    )
    (net (code "44") (name "Net-(J3-Pad4)") (class "Default")
      (node (ref "J3") (pin "4") (pinfunction "4_4") (pintype "passive"))
      (node (ref "R15") (pin "2") (pinfunction "2_2") (pintype "passive"))
    )
    (net (code "45") (name "Net-(J3-Pad5)") (class "Default")
      (node (ref "J3") (pin "5") (pinfunction "5_5") (pintype "passive"))
      (node (ref "R19") (pin "2") (pinfunction "2_2") (pintype "passive"))
    )
    (net (code "46") (name "Net-(J3-Pad6)") (class "Default")
      (node (ref "J3") (pin "6") (pinfunction "6_6") (pintype "passive"))
      (node (ref "R23") (pin "2") (pinfunction "2_2") (pintype "passive"))
    )
    (net (code "47") (name "Net-(J3-Pad7)") (class "Default")
      (node (ref "J3") (pin "7") (pinfunction "7_7") (pintype "passive"))
      (node (ref "R27") (pin "2") (pinfunction "2_2") (pintype "passive"))
    )
    (net (code "48") (name "Net-(J3-Pad8)") (class "Default")
      (node (ref "J3") (pin "8") (pinfunction "8_8") (pintype "passive"))
      (node (ref "R31") (pin "2") (pinfunction "2_2") (pintype "passive"))
    )
    (net (code "49") (name "Net-(J4-Pad1)") (class "Default")
      (node (ref "J4") (pin "1") (pinfunction "1_1") (pintype "passive"))
      (node (ref "R4") (pin "2") (pinfunction "2_2") (pintype "passive"))
    )
    (net (code "50") (name "Net-(J4-Pad2)") (class "Default")
      (node (ref "J4") (pin "2") (pinfunction "2_2") (pintype "passive"))
      (node (ref "R8") (pin "2") (pinfunction "2_2") (pintype "passive"))
    )
    (net (code "51") (name "Net-(J4-Pad3)") (class "Default")
      (node (ref "J4") (pin "3") (pinfunction "3_3") (pintype "passive"))
      (node (ref "R12") (pin "2") (pinfunction "2_2") (pintype "passive"))
    )
    (net (code "52") (name "Net-(J4-Pad4)") (class "Default")
      (node (ref "J4") (pin "4") (pinfunction "4_4") (pintype "passive"))
      (node (ref "R16") (pin "2") (pinfunction "2_2") (pintype "passive"))
    )
    (net (code "53") (name "Net-(J4-Pad5)") (class "Default")
      (node (ref "J4") (pin "5") (pinfunction "5_5") (pintype "passive"))
      (node (ref "R20") (pin "2") (pinfunction "2_2") (pintype "passive"))
    )
    (net (code "54") (name "Net-(J4-Pad6)") (class "Default")
      (node (ref "J4") (pin "6") (pinfunction "6_6") (pintype "passive"))
      (node (ref "R24") (pin "2") (pinfunction "2_2") (pintype "passive"))
    )
    (net (code "55") (name "Net-(J4-Pad7)") (class "Default")
      (node (ref "J4") (pin "7") (pinfunction "7_7") (pintype "passive"))
      (node (ref "R28") (pin "2") (pinfunction "2_2") (pintype "passive"))
    )
    (net (code "56") (name "Net-(J4-Pad8)") (class "Default")
      (node (ref "J4") (pin "8") (pinfunction "8_8") (pintype "passive"))
      (node (ref "R32") (pin "2") (pinfunction "2_2") (pintype "passive"))
    )
    (net (code "57") (name "Net-(J5-Pad1)") (class "Default")
      (node (ref "J5") (pin "1") (pinfunction "1_1") (pintype "passive"))
      (node (ref "R33") (pin "2") (pinfunction "2_2") (pintype "passive"))
    )
    (net (code "58") (name "Net-(J5-Pad2)") (class "Default")
      (node (ref "J5") (pin "2") (pinfunction "2_2") (pintype "passive"))
      (node (ref "R37") (pin "2") (pinfunction "2_2") (pintype "passive"))
    )
    (net (code "59") (name "Net-(J5-Pad3)") (class "Default")
      (node (ref "J5") (pin "3") (pinfunction "3_3") (pintype "passive"))
      (node (ref "R41") (pin "2") (pinfunction "2_2") (pintype "passive"))
    )
    (net (code "60") (name "Net-(J5-Pad4)") (class "Default")
      (node (ref "J5") (pin "4") (pinfunction "4_4") (pintype "passive"))
      (node (ref "R45") (pin "2") (pinfunction "2_2") (pintype "passive"))
    )
    (net (code "61") (name "Net-(J5-Pad5)") (class "Default")
      (node (ref "J5") (pin "5") (pinfunction "5_5") (pintype "passive"))
      (node (ref "R49") (pin "2") (pinfunction "2_2") (pintype "passive"))
    )
    (net (code "62") (name "Net-(J5-Pad6)") (class "Default")
      (node (ref "J5") (pin "6") (pinfunction "6_6") (pintype "passive"))
      (node (ref "R53") (pin "2") (pinfunction "2_2") (pintype "passive"))
    )
    (net (code "63") (name "Net-(J5-Pad7)") (class "Default")
      (node (ref "J5") (pin "7") (pinfunction "7_7") (pintype "passive"))
      (node (ref "R57") (pin "2") (pinfunction "2_2") (pintype "passive"))
    )
    (net (code "64") (name "Net-(J5-Pad8)") (class "Default")
      (node (ref "J5") (pin "8") (pinfunction "8_8") (pintype "passive"))
      (node (ref "R61") (pin "2") (pinfunction "2_2") (pintype "passive"))
    )
    (net (code "65") (name "Net-(J6-Pad1)") (class "Default")
      (node (ref "J6") (pin "1") (pinfunction "1_1") (pintype "passive"))
      (node (ref "R34") (pin "2") (pinfunction "2_2") (pintype "passive"))
    )
    (net (code "66") (name "Net-(J6-Pad2)") (class "Default")
      (node (ref "J6") (pin "2") (pinfunction "2_2") (pintype "passive"))
      (node (ref "R38") (pin "2") (pinfunction "2_2") (pintype "passive"))
    )
    (net (code "67") (name "Net-(J6-Pad3)") (class "Default")
      (node (ref "J6") (pin "3") (pinfunction "3_3") (pintype "passive"))
      (node (ref "R42") (pin "2") (pinfunction "2_2") (pintype "passive"))
    )
    (net (code "68") (name "Net-(J6-Pad4)") (class "Default")
      (node (ref "J6") (pin "4") (pinfunction "4_4") (pintype "passive"))
      (node (ref "R46") (pin "2") (pinfunction "2_2") (pintype "passive"))
    )
    (net (code "69") (name "Net-(J6-Pad5)") (class "Default")
      (node (ref "J6") (pin "5") (pinfunction "5_5") (pintype "passive"))
      (node (ref "R50") (pin "2") (pinfunction "2_2") (pintype "passive"))
    )
    (net (code "70") (name "Net-(J6-Pad6)") (class "Default")
      (node (ref "J6") (pin "6") (pinfunction "6_6") (pintype "passive"))
      (node (ref "R54") (pin "2") (pinfunction "2_2") (pintype "passive"))
    )
    (net (code "71") (name "Net-(J6-Pad7)") (class "Default")
      (node (ref "J6") (pin "7") (pinfunction "7_7") (pintype "passive"))
      (node (ref "R58") (pin "2") (pinfunction "2_2") (pintype "passive"))
    )
    (net (code "72") (name "Net-(J6-Pad8)") (class "Default")
      (node (ref "J6") (pin "8") (pinfunction "8_8") (pintype "passive"))
      (node (ref "R62") (pin "2") (pinfunction "2_2") (pintype "passive"))
    )
    (net (code "73") (name "Net-(J7-Pad1)") (class "Default")
      (node (ref "J7") (pin "1") (pinfunction "1_1") (pintype "passive"))
      (node (ref "R35") (pin "2") (pinfunction "2_2") (pintype "passive"))
    )
    (net (code "74") (name "Net-(J7-Pad2)") (class "Default")
      (node (ref "J7") (pin "2") (pinfunction "2_2") (pintype "passive"))
      (node (ref "R39") (pin "2") (pinfunction "2_2") (pintype "passive"))
    )
    (net (code "75") (name "Net-(J7-Pad3)") (class "Default")
      (node (ref "J7") (pin "3") (pinfunction "3_3") (pintype "passive"))
      (node (ref "R43") (pin "2") (pinfunction "2_2") (pintype "passive"))
    )
    (net (code "76") (name "Net-(J7-Pad4)") (class "Default")
      (node (ref "J7") (pin "4") (pinfunction "4_4") (pintype "passive"))
      (node (ref "R47") (pin "2") (pinfunction "2_2") (pintype "passive"))
    )
    (net (code "77") (name "Net-(J7-Pad5)") (class "Default")
      (node (ref "J7") (pin "5") (pinfunction "5_5") (pintype "passive"))
      (node (ref "R51") (pin "2") (pinfunction "2_2") (pintype "passive"))
    )
    (net (code "78") (name "Net-(J7-Pad6)") (class "Default")
      (node (ref "J7") (pin "6") (pinfunction "6_6") (pintype "passive"))
      (node (ref "R55") (pin "2") (pinfunction "2_2") (pintype "passive"))
    )
    (net (code "79") (name "Net-(J7-Pad7)") (class "Default")
      (node (ref "J7") (pin "7") (pinfunction "7_7") (pintype "passive"))
      (node (ref "R59") (pin "2") (pinfunction "2_2") (pintype "passive"))
    )
    (net (code "80") (name "Net-(J7-Pad8)") (class "Default")
      (node (ref "J7") (pin "8") (pinfunction "8_8") (pintype "passive"))
      (node (ref "R63") (pin "2") (pinfunction "2_2") (pintype "passive"))
    )
    (net (code "81") (name "Net-(J8-Pad1)") (class "Default")
      (node (ref "J8") (pin "1") (pinfunction "1_1") (pintype "passive"))
      (node (ref "R36") (pin "2") (pinfunction "2_2") (pintype "passive"))
    )
    (net (code "82") (name "Net-(J8-Pad2)") (class "Default")
      (node (ref "J8") (pin "2") (pinfunction "2_2") (pintype "passive"))
      (node (ref "R40") (pin "2") (pinfunction "2_2") (pintype "passive"))
    )
    (net (code "83") (name "Net-(J8-Pad3)") (class "Default")
      (node (ref "J8") (pin "3") (pinfunction "3_3") (pintype "passive"))
      (node (ref "R44") (pin "2") (pinfunction "2_2") (pintype "passive"))
    )
    (net (code "84") (name "Net-(J8-Pad4)") (class "Default")
      (node (ref "J8") (pin "4") (pinfunction "4_4") (pintype "passive"))
      (node (ref "R48") (pin "2") (pinfunction "2_2") (pintype "passive"))
    )
    (net (code "85") (name "Net-(J8-Pad5)") (class "Default")
      (node (ref "J8") (pin "5") (pinfunction "5_5") (pintype "passive"))
      (node (ref "R52") (pin "2") (pinfunction "2_2") (pintype "passive"))
    )
    (net (code "86") (name "Net-(J8-Pad6)") (class "Default")
      (node (ref "J8") (pin "6") (pinfunction "6_6") (pintype "passive"))
      (node (ref "R56") (pin "2") (pinfunction "2_2") (pintype "passive"))
    )
    (net (code "87") (name "Net-(J8-Pad7)") (class "Default")
      (node (ref "J8") (pin "7") (pinfunction "7_7") (pintype "passive"))
      (node (ref "R60") (pin "2") (pinfunction "2_2") (pintype "passive"))
    )
    (net (code "88") (name "Net-(J8-Pad8)") (class "Default")
      (node (ref "J8") (pin "8") (pinfunction "8_8") (pintype "passive"))
      (node (ref "R64") (pin "2") (pinfunction "2_2") (pintype "passive"))
    )
    (net (code "89") (name "Net-(U1-1Q)") (class "Default")
      (node (ref "R1") (pin "1") (pinfunction "1_1") (pintype "passive"))
      (node (ref "U1") (pin "19") (pinfunction "1Q_19") (pintype "passive"))
    )
    (net (code "90") (name "Net-(U1-2Q)") (class "Default")
      (node (ref "R5") (pin "1") (pinfunction "1_1") (pintype "passive"))
      (node (ref "U1") (pin "18") (pinfunction "2Q_18") (pintype "passive"))
    )
    (net (code "91") (name "Net-(U1-3Q)") (class "Default")
      (node (ref "R9") (pin "1") (pinfunction "1_1") (pintype "passive"))
      (node (ref "U1") (pin "17") (pinfunction "3Q_17") (pintype "passive"))
    )
    (net (code "92") (name "Net-(U1-4Q)") (class "Default")
      (node (ref "R13") (pin "1") (pinfunction "1_1") (pintype "passive"))
      (node (ref "U1") (pin "16") (pinfunction "4Q_16") (pintype "passive"))
    )
    (net (code "93") (name "Net-(U1-5Q)") (class "Default")
      (node (ref "R17") (pin "1") (pinfunction "1_1") (pintype "passive"))
      (node (ref "U1") (pin "15") (pinfunction "5Q_15") (pintype "passive"))
    )
    (net (code "94") (name "Net-(U1-6Q)") (class "Default")
      (node (ref "R21") (pin "1") (pinfunction "1_1") (pintype "passive"))
      (node (ref "U1") (pin "14") (pinfunction "6Q_14") (pintype "passive"))
    )
    (net (code "95") (name "Net-(U1-7Q)") (class "Default")
      (node (ref "R25") (pin "1") (pinfunction "1_1") (pintype "passive"))
      (node (ref "U1") (pin "13") (pinfunction "7Q_13") (pintype "passive"))
    )
    (net (code "96") (name "Net-(U1-8Q)") (class "Default")
      (node (ref "R29") (pin "1") (pinfunction "1_1") (pintype "passive"))
      (node (ref "U1") (pin "12") (pinfunction "8Q_12") (pintype "passive"))
    )
    (net (code "97") (name "Net-(U2-1Q)") (class "Default")
      (node (ref "R2") (pin "1") (pinfunction "1_1") (pintype "passive"))
      (node (ref "U2") (pin "19") (pinfunction "1Q_19") (pintype "passive"))
    )
    (net (code "98") (name "Net-(U2-2Q)") (class "Default")
      (node (ref "R6") (pin "1") (pinfunction "1_1") (pintype "passive"))
      (node (ref "U2") (pin "18") (pinfunction "2Q_18") (pintype "passive"))
    )
    (net (code "99") (name "Net-(U2-3Q)") (class "Default")
      (node (ref "R10") (pin "1") (pinfunction "1_1") (pintype "passive"))
      (node (ref "U2") (pin "17") (pinfunction "3Q_17") (pintype "passive"))
    )
    (net (code "100") (name "Net-(U2-4Q)") (class "Default")
      (node (ref "R14") (pin "1") (pinfunction "1_1") (pintype "passive"))
      (node (ref "U2") (pin "16") (pinfunction "4Q_16") (pintype "passive"))
    )
    (net (code "101") (name "Net-(U2-5Q)") (class "Default")
      (node (ref "R18") (pin "1") (pinfunction "1_1") (pintype "passive"))
      (node (ref "U2") (pin "15") (pinfunction "5Q_15") (pintype "passive"))
    )
    (net (code "102") (name "Net-(U2-6Q)") (class "Default")
      (node (ref "R22") (pin "1") (pinfunction "1_1") (pintype "passive"))
      (node (ref "U2") (pin "14") (pinfunction "6Q_14") (pintype "passive"))
    )
    (net (code "103") (name "Net-(U2-7Q)") (class "Default")
      (node (ref "R26") (pin "1") (pinfunction "1_1") (pintype "passive"))
      (node (ref "U2") (pin "13") (pinfunction "7Q_13") (pintype "passive"))
    )
    (net (code "104") (name "Net-(U2-8Q)") (class "Default")
      (node (ref "R30") (pin "1") (pinfunction "1_1") (pintype "passive"))
      (node (ref "U2") (pin "12") (pinfunction "8Q_12") (pintype "passive"))
    )
    (net (code "105") (name "Net-(U3-1Q)") (class "Default")
      (node (ref "R3") (pin "1") (pinfunction "1_1") (pintype "passive"))
      (node (ref "U3") (pin "19") (pinfunction "1Q_19") (pintype "passive"))
    )
    (net (code "106") (name "Net-(U3-2Q)") (class "Default")
      (node (ref "R7") (pin "1") (pinfunction "1_1") (pintype "passive"))
      (node (ref "U3") (pin "18") (pinfunction "2Q_18") (pintype "passive"))
    )
    (net (code "107") (name "Net-(U3-3Q)") (class "Default")
      (node (ref "R11") (pin "1") (pinfunction "1_1") (pintype "passive"))
      (node (ref "U3") (pin "17") (pinfunction "3Q_17") (pintype "passive"))
    )
    (net (code "108") (name "Net-(U3-4Q)") (class "Default")
      (node (ref "R15") (pin "1") (pinfunction "1_1") (pintype "passive"))
      (node (ref "U3") (pin "16") (pinfunction "4Q_16") (pintype "passive"))
    )
    (net (code "109") (name "Net-(U3-5Q)") (class "Default")
      (node (ref "R19") (pin "1") (pinfunction "1_1") (pintype "passive"))
      (node (ref "U3") (pin "15") (pinfunction "5Q_15") (pintype "passive"))
    )
    (net (code "110") (name "Net-(U3-6Q)") (class "Default")
      (node (ref "R23") (pin "1") (pinfunction "1_1") (pintype "passive"))
      (node (ref "U3") (pin "14") (pinfunction "6Q_14") (pintype "passive"))
    )
    (net (code "111") (name "Net-(U3-7Q)") (class "Default")
      (node (ref "R27") (pin "1") (pinfunction "1_1") (pintype "passive"))
      (node (ref "U3") (pin "13") (pinfunction "7Q_13") (pintype "passive"))
    )
    (net (code "112") (name "Net-(U3-8Q)") (class "Default")
      (node (ref "R31") (pin "1") (pinfunction "1_1") (pintype "passive"))
      (node (ref "U3") (pin "12") (pinfunction "8Q_12") (pintype "passive"))
    )
    (net (code "113") (name "Net-(U4-1Q)") (class "Default")
      (node (ref "R4") (pin "1") (pinfunction "1_1") (pintype "passive"))
      (node (ref "U4") (pin "19") (pinfunction "1Q_19") (pintype "passive"))
    )
    (net (code "114") (name "Net-(U4-2Q)") (class "Default")
      (node (ref "R8") (pin "1") (pinfunction "1_1") (pintype "passive"))
      (node (ref "U4") (pin "18") (pinfunction "2Q_18") (pintype "passive"))
    )
    (net (code "115") (name "Net-(U4-3Q)") (class "Default")
      (node (ref "R12") (pin "1") (pinfunction "1_1") (pintype "passive"))
      (node (ref "U4") (pin "17") (pinfunction "3Q_17") (pintype "passive"))
    )
    (net (code "116") (name "Net-(U4-4Q)") (class "Default")
      (node (ref "R16") (pin "1") (pinfunction "1_1") (pintype "passive"))
      (node (ref "U4") (pin "16") (pinfunction "4Q_16") (pintype "passive"))
    )
    (net (code "117") (name "Net-(U4-5Q)") (class "Default")
      (node (ref "R20") (pin "1") (pinfunction "1_1") (pintype "passive"))
      (node (ref "U4") (pin "15") (pinfunction "5Q_15") (pintype "passive"))
    )
    (net (code "118") (name "Net-(U4-6Q)") (class "Default")
      (node (ref "R24") (pin "1") (pinfunction "1_1") (pintype "passive"))
      (node (ref "U4") (pin "14") (pinfunction "6Q_14") (pintype "passive"))
    )
    (net (code "119") (name "Net-(U4-7Q)") (class "Default")
      (node (ref "R28") (pin "1") (pinfunction "1_1") (pintype "passive"))
      (node (ref "U4") (pin "13") (pinfunction "7Q_13") (pintype "passive"))
    )
    (net (code "120") (name "Net-(U4-8Q)") (class "Default")
      (node (ref "R32") (pin "1") (pinfunction "1_1") (pintype "passive"))
      (node (ref "U4") (pin "12") (pinfunction "8Q_12") (pintype "passive"))
    )
    (net (code "121") (name "Net-(U5-1Q)") (class "Default")
      (node (ref "R33") (pin "1") (pinfunction "1_1") (pintype "passive"))
      (node (ref "U5") (pin "19") (pinfunction "1Q_19") (pintype "passive"))
    )
    (net (code "122") (name "Net-(U5-2Q)") (class "Default")
      (node (ref "R37") (pin "1") (pinfunction "1_1") (pintype "passive"))
      (node (ref "U5") (pin "18") (pinfunction "2Q_18") (pintype "passive"))
    )
    (net (code "123") (name "Net-(U5-3Q)") (class "Default")
      (node (ref "R41") (pin "1") (pinfunction "1_1") (pintype "passive"))
      (node (ref "U5") (pin "17") (pinfunction "3Q_17") (pintype "passive"))
    )
    (net (code "124") (name "Net-(U5-4Q)") (class "Default")
      (node (ref "R45") (pin "1") (pinfunction "1_1") (pintype "passive"))
      (node (ref "U5") (pin "16") (pinfunction "4Q_16") (pintype "passive"))
    )
    (net (code "125") (name "Net-(U5-5Q)") (class "Default")
      (node (ref "R49") (pin "1") (pinfunction "1_1") (pintype "passive"))
      (node (ref "U5") (pin "15") (pinfunction "5Q_15") (pintype "passive"))
    )
    (net (code "126") (name "Net-(U5-6Q)") (class "Default")
      (node (ref "R53") (pin "1") (pinfunction "1_1") (pintype "passive"))
      (node (ref "U5") (pin "14") (pinfunction "6Q_14") (pintype "passive"))
    )
    (net (code "127") (name "Net-(U5-7Q)") (class "Default")
      (node (ref "R57") (pin "1") (pinfunction "1_1") (pintype "passive"))
      (node (ref "U5") (pin "13") (pinfunction "7Q_13") (pintype "passive"))
    )
    (net (code "128") (name "Net-(U5-8Q)") (class "Default")
      (node (ref "R61") (pin "1") (pinfunction "1_1") (pintype "passive"))
      (node (ref "U5") (pin "12") (pinfunction "8Q_12") (pintype "passive"))
    )
    (net (code "129") (name "Net-(U6-1Q)") (class "Default")
      (node (ref "R34") (pin "1") (pinfunction "1_1") (pintype "passive"))
      (node (ref "U6") (pin "19") (pinfunction "1Q_19") (pintype "passive"))
    )
    (net (code "130") (name "Net-(U6-2Q)") (class "Default")
      (node (ref "R38") (pin "1") (pinfunction "1_1") (pintype "passive"))
      (node (ref "U6") (pin "18") (pinfunction "2Q_18") (pintype "passive"))
    )
    (net (code "131") (name "Net-(U6-3Q)") (class "Default")
      (node (ref "R42") (pin "1") (pinfunction "1_1") (pintype "passive"))
      (node (ref "U6") (pin "17") (pinfunction "3Q_17") (pintype "passive"))
    )
    (net (code "132") (name "Net-(U6-4Q)") (class "Default")
      (node (ref "R46") (pin "1") (pinfunction "1_1") (pintype "passive"))
      (node (ref "U6") (pin "16") (pinfunction "4Q_16") (pintype "passive"))
    )
    (net (code "133") (name "Net-(U6-5Q)") (class "Default")
      (node (ref "R50") (pin "1") (pinfunction "1_1") (pintype "passive"))
      (node (ref "U6") (pin "15") (pinfunction "5Q_15") (pintype "passive"))
    )
    (net (code "134") (name "Net-(U6-6Q)") (class "Default")
      (node (ref "R54") (pin "1") (pinfunction "1_1") (pintype "passive"))
      (node (ref "U6") (pin "14") (pinfunction "6Q_14") (pintype "passive"))
    )
    (net (code "135") (name "Net-(U6-7Q)") (class "Default")
      (node (ref "R58") (pin "1") (pinfunction "1_1") (pintype "passive"))
      (node (ref "U6") (pin "13") (pinfunction "7Q_13") (pintype "passive"))
    )
    (net (code "136") (name "Net-(U6-8Q)") (class "Default")
      (node (ref "R62") (pin "1") (pinfunction "1_1") (pintype "passive"))
      (node (ref "U6") (pin "12") (pinfunction "8Q_12") (pintype "passive"))
    )
    (net (code "137") (name "Net-(U7-1Q)") (class "Default")
      (node (ref "R35") (pin "1") (pinfunction "1_1") (pintype "passive"))
      (node (ref "U7") (pin "19") (pinfunction "1Q_19") (pintype "passive"))
    )
    (net (code "138") (name "Net-(U7-2Q)") (class "Default")
      (node (ref "R39") (pin "1") (pinfunction "1_1") (pintype "passive"))
      (node (ref "U7") (pin "18") (pinfunction "2Q_18") (pintype "passive"))
    )
    (net (code "139") (name "Net-(U7-3Q)") (class "Default")
      (node (ref "R43") (pin "1") (pinfunction "1_1") (pintype "passive"))
      (node (ref "U7") (pin "17") (pinfunction "3Q_17") (pintype "passive"))
    )
    (net (code "140") (name "Net-(U7-4Q)") (class "Default")
      (node (ref "R47") (pin "1") (pinfunction "1_1") (pintype "passive"))
      (node (ref "U7") (pin "16") (pinfunction "4Q_16") (pintype "passive"))
    )
    (net (code "141") (name "Net-(U7-5Q)") (class "Default")
      (node (ref "R51") (pin "1") (pinfunction "1_1") (pintype "passive"))
      (node (ref "U7") (pin "15") (pinfunction "5Q_15") (pintype "passive"))
    )
    (net (code "142") (name "Net-(U7-6Q)") (class "Default")
      (node (ref "R55") (pin "1") (pinfunction "1_1") (pintype "passive"))
      (node (ref "U7") (pin "14") (pinfunction "6Q_14") (pintype "passive"))
    )
    (net (code "143") (name "Net-(U7-7Q)") (class "Default")
      (node (ref "R59") (pin "1") (pinfunction "1_1") (pintype "passive"))
      (node (ref "U7") (pin "13") (pinfunction "7Q_13") (pintype "passive"))
    )
    (net (code "144") (name "Net-(U7-8Q)") (class "Default")
      (node (ref "R63") (pin "1") (pinfunction "1_1") (pintype "passive"))
      (node (ref "U7") (pin "12") (pinfunction "8Q_12") (pintype "passive"))
    )
    (net (code "145") (name "Net-(U8-1Q)") (class "Default")
      (node (ref "R36") (pin "1") (pinfunction "1_1") (pintype "passive"))
      (node (ref "U8") (pin "19") (pinfunction "1Q_19") (pintype "passive"))
    )
    (net (code "146") (name "Net-(U8-2Q)") (class "Default")
      (node (ref "R40") (pin "1") (pinfunction "1_1") (pintype "passive"))
      (node (ref "U8") (pin "18") (pinfunction "2Q_18") (pintype "passive"))
    )
    (net (code "147") (name "Net-(U8-3Q)") (class "Default")
      (node (ref "R44") (pin "1") (pinfunction "1_1") (pintype "passive"))
      (node (ref "U8") (pin "17") (pinfunction "3Q_17") (pintype "passive"))
    )
    (net (code "148") (name "Net-(U8-4Q)") (class "Default")
      (node (ref "R48") (pin "1") (pinfunction "1_1") (pintype "passive"))
      (node (ref "U8") (pin "16") (pinfunction "4Q_16") (pintype "passive"))
    )
    (net (code "149") (name "Net-(U8-5Q)") (class "Default")
      (node (ref "R52") (pin "1") (pinfunction "1_1") (pintype "passive"))
      (node (ref "U8") (pin "15") (pinfunction "5Q_15") (pintype "passive"))
    )
    (net (code "150") (name "Net-(U8-6Q)") (class "Default")
      (node (ref "R56") (pin "1") (pinfunction "1_1") (pintype "passive"))
      (node (ref "U8") (pin "14") (pinfunction "6Q_14") (pintype "passive"))
    )
    (net (code "151") (name "Net-(U8-7Q)") (class "Default")
      (node (ref "R60") (pin "1") (pinfunction "1_1") (pintype "passive"))
      (node (ref "U8") (pin "13") (pinfunction "7Q_13") (pintype "passive"))
    )
    (net (code "152") (name "Net-(U8-8Q)") (class "Default")
      (node (ref "R64") (pin "1") (pinfunction "1_1") (pintype "passive"))
      (node (ref "U8") (pin "12") (pinfunction "8Q_12") (pintype "passive"))
    )
  )
)
